# CAN_Tester_Board_Rev3.net
KiCad netlist of a schematic drawn in EAGLE
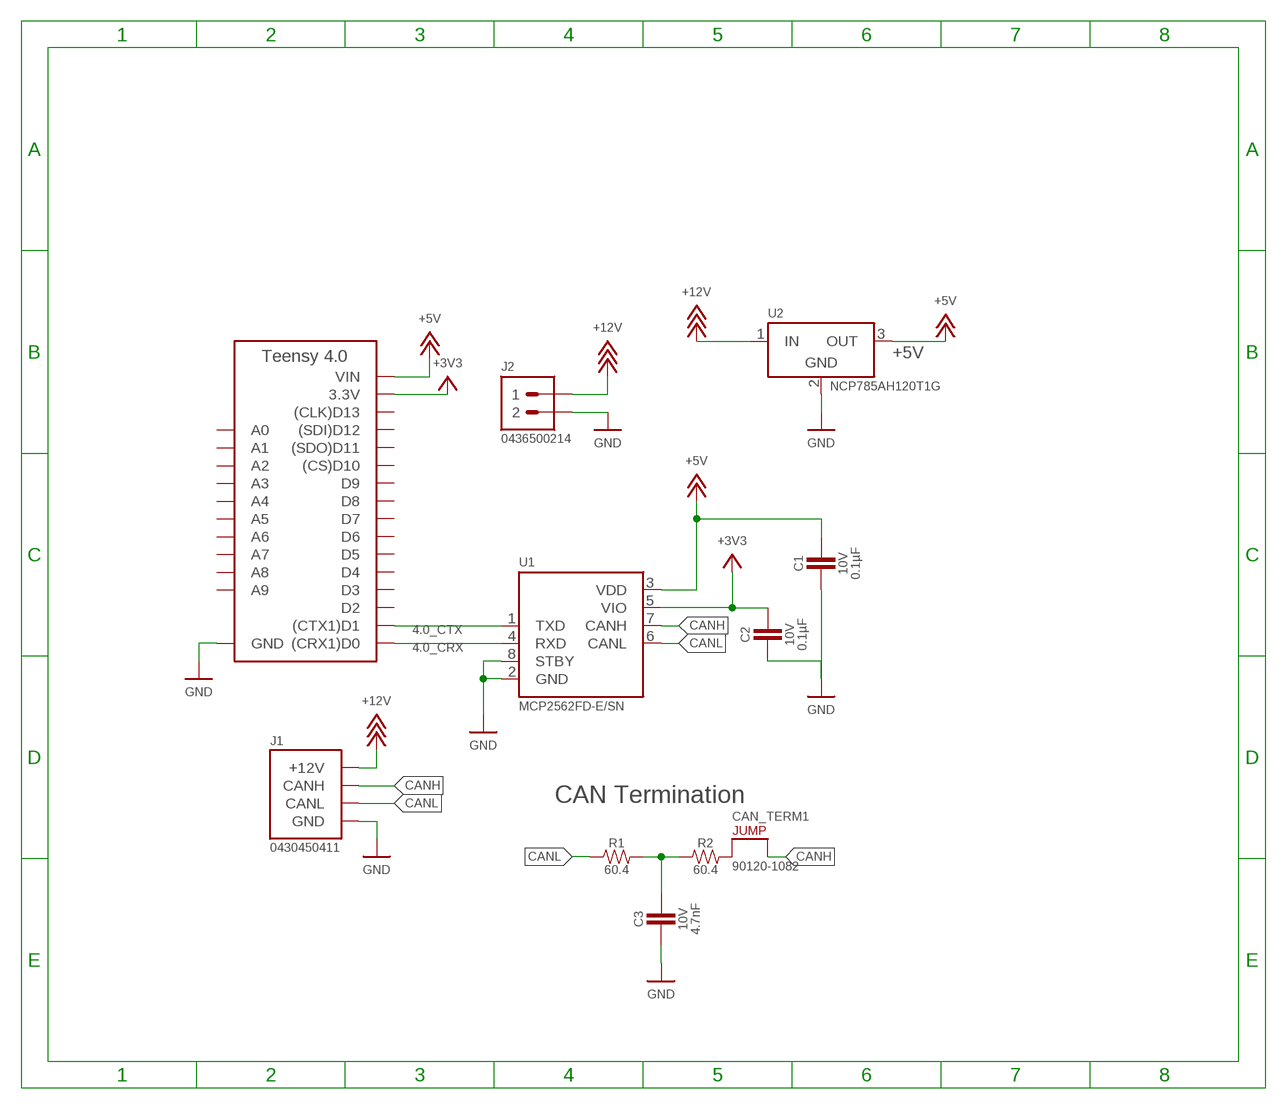
[diagram p0: schematic, sheet 1]

(export (version "E")
  (design (tool "Eeschema 10.0.6"))
  (components
    (comp (ref "A1")
      (value "TEENSY_4.0")
      (footprint "eagle-import:TEENSY_SHORT")
      (libsource (lib "eagle-import") (part "TEENSY_4.0"))
    )
    (comp (ref "C1")
      (value "CAPACITOR_0603_10V_0.1UF")
      (footprint "eagle-import:0603-CAP")
      (fields
        (field (name "CAPACITANCE") "0.1µF")
        (field (name "MANUFACTURER") "Vishay Vitramon")
        (field (name "MPN") "VJ0603Y104JXQPW1BC")
        (field (name "TOLERANCE") "5%")
        (field (name "VOLTAGE") "10V")
      )
      (libsource (lib "eagle-import") (part "CAPACITOR_?_060310V_0.1UF"))
    )
    (comp (ref "C2")
      (value "CAPACITOR_0603_10V_0.1UF")
      (footprint "eagle-import:0603-CAP")
      (fields
        (field (name "CAPACITANCE") "0.1µF")
        (field (name "MANUFACTURER") "Vishay Vitramon")
        (field (name "MPN") "VJ0603Y104JXQPW1BC")
        (field (name "TOLERANCE") "5%")
        (field (name "VOLTAGE") "10V")
      )
      (libsource (lib "eagle-import") (part "CAPACITOR_?_060310V_0.1UF"))
    )
    (comp (ref "C3")
      (value "CAPACITOR_0603_10V_4.7NF")
      (footprint "eagle-import:0603-CAP")
      (fields
        (field (name "CAPACITANCE") "4.7nF")
        (field (name "MANUFACTURER") "Würth Elektronik")
        (field (name "MPN") "885012206012")
        (field (name "TOLERANCE") "10%")
        (field (name "VOLTAGE") "10V")
      )
      (libsource (lib "eagle-import") (part "CAPACITOR_?_060310V_4.7NF"))
    )
    (comp (ref "CAN_TERM1")
      (value "JUMPER__1X02")
      (footprint "eagle-import:1X02")
      (fields (field (name "MANUFACTURER") "Molex") (field (name "MPN") "90120-1082 "))
      (libsource (lib "eagle-import") (part "JUMPER_?_1X02"))
    )
    (comp (ref "J1")
      (value "CONNECTOR-CAN_μF_S_RA_")
      (footprint "eagle-import:MOLEX_MICROFIT_SMD_RIGHTANGLE_04_DUAL")
      (fields (field (name "MPN") "0430450411") (field (name "MANUFACTURER") "Molex"))
      (libsource (lib "eagle-import") (part "CONNECTOR-CAN_?_μF_S_RA"))
    )
    (comp (ref "J2")
      (value "CONNECTOR-2_MICROFIT_SMD_RIGHTANGLE_02_SINGLE_BLACK")
      (footprint "eagle-import:MOLEX_MICROFIT_SMD_RIGHTANGLE_02_SINGLE")
      (fields (field (name "MANUFACTURER") "Molex") (field (name "MPN") "0436500214"))
      (libsource (lib "eagle-import") (part "CONNECTOR-2_?_MICROFIT_SMD_RIGHTANGLE_02_SINGLEBLACK"))
    )
    (comp (ref "R1")
      (value "RESISTOR_0603_60.4")
      (footprint "eagle-import:0603-RES")
      (fields
        (field (name "MANUFACTURER") "Yageo")
        (field (name "MPN") "RC0603FR-0760R4L")
        (field (name "POWER") "0.1W")
        (field (name "RESISTANCE") "60.4")
      )
      (libsource (lib "eagle-import") (part "RESISTOR_?_060360.4"))
    )
    (comp (ref "R2")
      (value "RESISTOR_0603_60.4")
      (footprint "eagle-import:0603-RES")
      (fields
        (field (name "MANUFACTURER") "Yageo")
        (field (name "MPN") "RC0603FR-0760R4L")
        (field (name "POWER") "0.1W")
        (field (name "RESISTANCE") "60.4")
      )
      (libsource (lib "eagle-import") (part "RESISTOR_?_060360.4"))
    )
    (comp (ref "U1")
      (value "MCP2562FD")
      (footprint "eagle-import:SOIC-08(NARROW,0.15_)")
      (fields (field (name "MPN") "MCP2562FD-E/SN") (field (name "MANUFACTURER") "Microchip Technology"))
      (libsource (lib "eagle-import") (part "MCP2562FD"))
    )
    (comp (ref "U2")
      (value "VOLTAGE_REGULATOR_SOT-89_12V")
      (footprint "eagle-import:SOT-89")
      (fields (field (name "MANUFACTURER") "ON Semiconductor") (field (name "MPN") "NCP785AH120T1G"))
      (libsource (lib "eagle-import") (part "VOLTAGE_REGULATOR_?_SOT-8912V"))
    )
  )
  (nets
    (net (code "1") (name "+3V3") (class "Default")
      (node (ref "A1") (pin "3.3V") (pinfunction "3.3V_3.3V") (pintype "power_in"))
      (node (ref "C2") (pin "1") (pinfunction "1_1") (pintype "passive"))
      (node (ref "U1") (pin "5") (pinfunction "VIO_5") (pintype "power_in"))
    )
    (net (code "2") (name "+5V") (class "Default")
      (node (ref "A1") (pin "VIN") (pinfunction "VIN_VIN") (pintype "power_in"))
      (node (ref "C1") (pin "1") (pinfunction "1_1") (pintype "passive"))
      (node (ref "U1") (pin "3") (pinfunction "VDD_3") (pintype "power_in"))
      (node (ref "U2") (pin "3") (pinfunction "OUT_3") (pintype "power_in"))
    )
    (net (code "3") (name "+12V") (class "Default")
      (node (ref "J1") (pin "1") (pinfunction "+12V_1") (pintype "power_in"))
      (node (ref "J2") (pin "1") (pinfunction "1_1") (pintype "passive"))
      (node (ref "U2") (pin "1") (pinfunction "IN_1") (pintype "power_in"))
    )
    (net (code "4") (name "/4.0_CRX") (class "Default")
      (node (ref "A1") (pin "D0") (pinfunction "(CRX1)D0_D0") (pintype "bidirectional"))
      (node (ref "U1") (pin "4") (pinfunction "RXD_4") (pintype "output"))
    )
    (net (code "5") (name "/4.0_CTX") (class "Default")
      (node (ref "A1") (pin "D1") (pinfunction "(CTX1)D1_D1") (pintype "bidirectional"))
      (node (ref "U1") (pin "1") (pinfunction "TXD_1") (pintype "input"))
    )
    (net (code "6") (name "CANH") (class "Default")
      (node (ref "CAN_TERM1") (pin "2") (pinfunction "2_2") (pintype "passive"))
      (node (ref "J1") (pin "4") (pinfunction "CANH_4") (pintype "bidirectional"))
      (node (ref "U1") (pin "7") (pinfunction "CANH_7") (pintype "bidirectional"))
    )
    (net (code "7") (name "CANL") (class "Default")
      (node (ref "J1") (pin "3") (pinfunction "CANL_3") (pintype "bidirectional"))
      (node (ref "R1") (pin "1") (pinfunction "1_1") (pintype "passive"))
      (node (ref "U1") (pin "6") (pinfunction "CANL_6") (pintype "bidirectional"))
    )
    (net (code "8") (name "GND") (class "Default")
      (node (ref "A1") (pin "AGND/GND") (pinfunction "GND_AGND/GND") (pintype "power_in"))
      (node (ref "A1") (pin "GND") (pinfunction "GND_GND") (pintype "power_in"))
      (node (ref "C1") (pin "2") (pinfunction "2_2") (pintype "passive"))
      (node (ref "C2") (pin "2") (pinfunction "2_2") (pintype "passive"))
      (node (ref "C3") (pin "2") (pinfunction "2_2") (pintype "passive"))
      (node (ref "J1") (pin "2") (pinfunction "GND_2") (pintype "power_in"))
      (node (ref "J2") (pin "2") (pinfunction "2_2") (pintype "passive"))
      (node (ref "U1") (pin "2") (pinfunction "GND_2") (pintype "power_in"))
      (node (ref "U1") (pin "8") (pinfunction "STBY_8") (pintype "passive"))
      (node (ref "U2") (pin "2") (pinfunction "GND_2") (pintype "power_in"))
    )
    (net (code "9") (name "Net-(C3-Pad1)") (class "Default")
      (node (ref "C3") (pin "1") (pinfunction "1_1") (pintype "passive"))
      (node (ref "R1") (pin "2") (pinfunction "2_2") (pintype "passive"))
      (node (ref "R2") (pin "1") (pinfunction "1_1") (pintype "passive"))
    )
    (net (code "10") (name "Net-(CAN_TERM1-Pad1)") (class "Default")
      (node (ref "CAN_TERM1") (pin "1") (pinfunction "1_1") (pintype "passive"))
      (node (ref "R2") (pin "2") (pinfunction "2_2") (pintype "passive"))
    )
    (net (code "11") (name "unconnected-(A1-(CLK)D13-PadD13)") (class "Default")
      (node (ref "A1") (pin "D13") (pinfunction "(CLK)D13_D13") (pintype "bidirectional"))
    )
    (net (code "12") (name "unconnected-(A1-(CS)D10-PadD10)") (class "Default")
      (node (ref "A1") (pin "D10") (pinfunction "(CS)D10_D10") (pintype "bidirectional"))
    )
    (net (code "13") (name "unconnected-(A1-(SDI)D12-PadD12)") (class "Default")
      (node (ref "A1") (pin "D12") (pinfunction "(SDI)D12_D12") (pintype "bidirectional"))
    )
    (net (code "14") (name "unconnected-(A1-(SDO)D11-PadD11)") (class "Default")
      (node (ref "A1") (pin "D11") (pinfunction "(SDO)D11_D11") (pintype "bidirectional"))
    )
    (net (code "15") (name "unconnected-(A1-A0-PadD14)") (class "Default")
      (node (ref "A1") (pin "D14") (pinfunction "A0_D14") (pintype "bidirectional"))
    )
    (net (code "16") (name "unconnected-(A1-A1-PadD15)") (class "Default")
      (node (ref "A1") (pin "D15") (pinfunction "A1_D15") (pintype "bidirectional"))
    )
    (net (code "17") (name "unconnected-(A1-A2-PadD16)") (class "Default")
      (node (ref "A1") (pin "D16") (pinfunction "A2_D16") (pintype "bidirectional"))
    )
    (net (code "18") (name "unconnected-(A1-A3-PadD17)") (class "Default")
      (node (ref "A1") (pin "D17") (pinfunction "A3_D17") (pintype "bidirectional"))
    )
    (net (code "19") (name "unconnected-(A1-A4-PadD18)") (class "Default")
      (node (ref "A1") (pin "D18") (pinfunction "A4_D18") (pintype "bidirectional"))
    )
    (net (code "20") (name "unconnected-(A1-A5-PadD19)") (class "Default")
      (node (ref "A1") (pin "D19") (pinfunction "A5_D19") (pintype "bidirectional"))
    )
    (net (code "21") (name "unconnected-(A1-A6-PadD20)") (class "Default")
      (node (ref "A1") (pin "D20") (pinfunction "A6_D20") (pintype "bidirectional"))
    )
    (net (code "22") (name "unconnected-(A1-A7-PadD21)") (class "Default")
      (node (ref "A1") (pin "D21") (pinfunction "A7_D21") (pintype "bidirectional"))
    )
    (net (code "23") (name "unconnected-(A1-A8-PadD22)") (class "Default")
      (node (ref "A1") (pin "D22") (pinfunction "A8_D22") (pintype "bidirectional"))
    )
    (net (code "24") (name "unconnected-(A1-A9-PadD23)") (class "Default")
      (node (ref "A1") (pin "D23") (pinfunction "A9_D23") (pintype "bidirectional"))
    )
    (net (code "25") (name "unconnected-(A1-PadD2)") (class "Default")
      (node (ref "A1") (pin "D2") (pinfunction "D2_D2") (pintype "bidirectional"))
    )
    (net (code "26") (name "unconnected-(A1-PadD3)") (class "Default")
      (node (ref "A1") (pin "D3") (pinfunction "D3_D3") (pintype "bidirectional"))
    )
    (net (code "27") (name "unconnected-(A1-PadD4)") (class "Default")
      (node (ref "A1") (pin "D4") (pinfunction "D4_D4") (pintype "bidirectional"))
    )
    (net (code "28") (name "unconnected-(A1-PadD5)") (class "Default")
      (node (ref "A1") (pin "D5") (pinfunction "D5_D5") (pintype "bidirectional"))
    )
    (net (code "29") (name "unconnected-(A1-PadD6)") (class "Default")
      (node (ref "A1") (pin "D6") (pinfunction "D6_D6") (pintype "bidirectional"))
    )
    (net (code "30") (name "unconnected-(A1-PadD7)") (class "Default")
      (node (ref "A1") (pin "D7") (pinfunction "D7_D7") (pintype "bidirectional"))
    )
    (net (code "31") (name "unconnected-(A1-PadD8)") (class "Default")
      (node (ref "A1") (pin "D8") (pinfunction "D8_D8") (pintype "bidirectional"))
    )
    (net (code "32") (name "unconnected-(A1-PadD9)") (class "Default")
      (node (ref "A1") (pin "D9") (pinfunction "D9_D9") (pintype "bidirectional"))
    )
  )
)
